# WallLightRemote_V1_0_MCU.net
KiCad netlist of a schematic drawn in Altium Designer
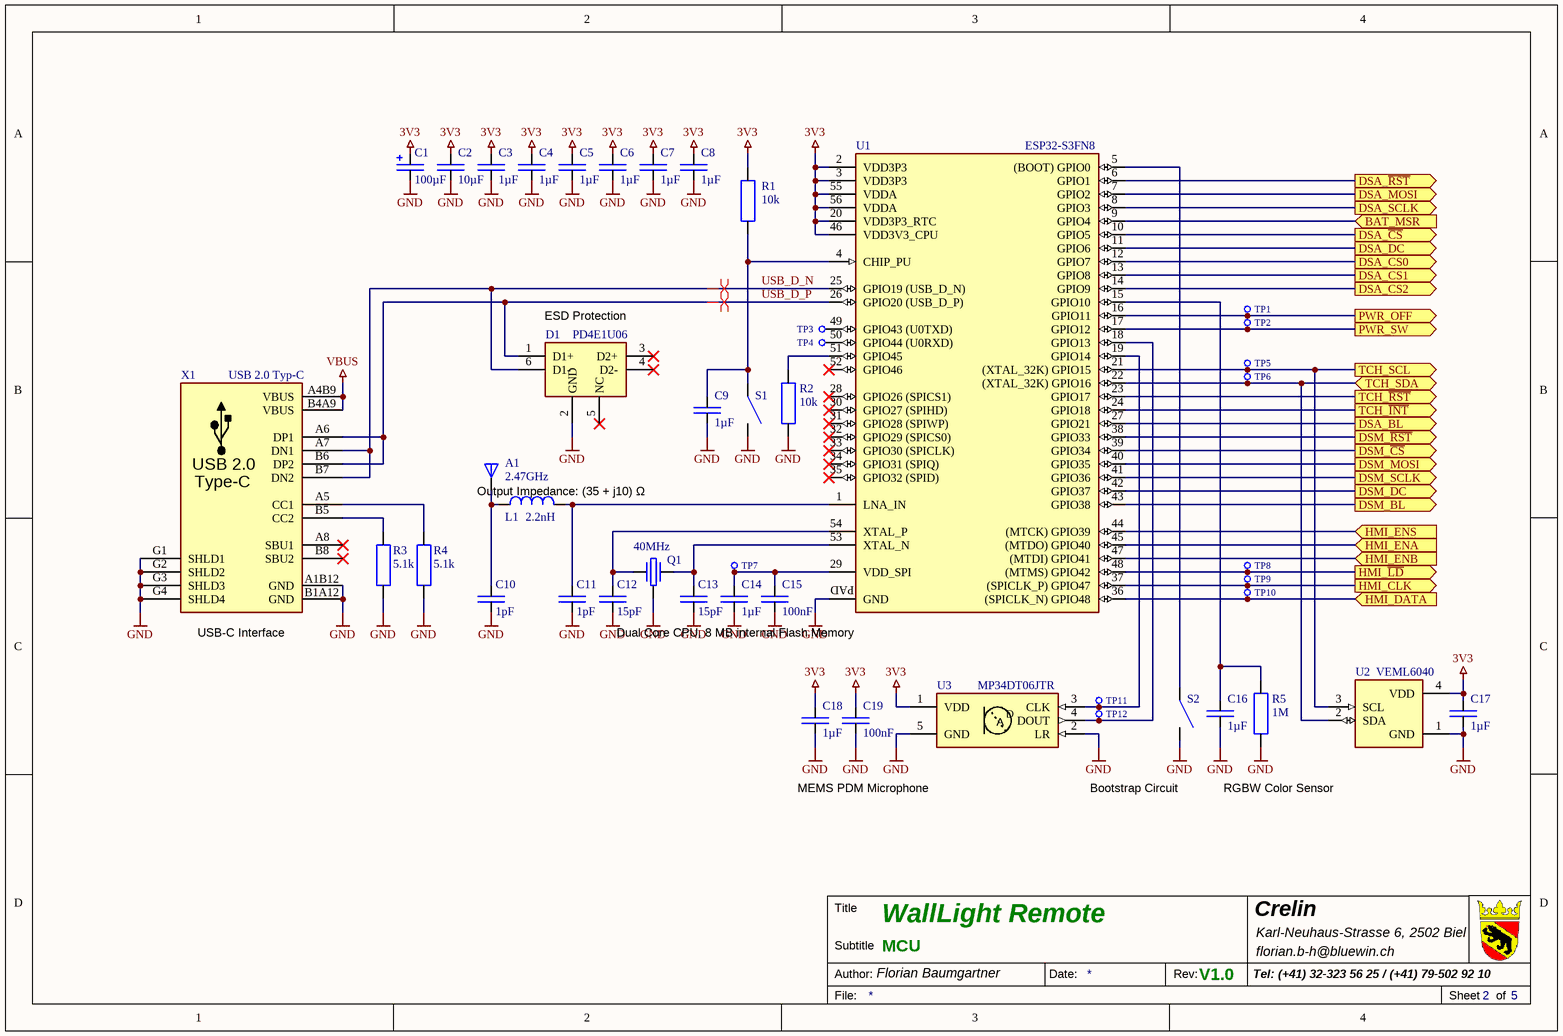
[diagram p0: WallLightRemote_V1.0_MCU.SchDoc]

(export (version "E")
  (design (tool "Eeschema 10.0.6"))
  (components
    (comp (ref "A1")
      (value "2.47GHz")
      (footprint "SMD Chip-Antenna 7020 (SLDA72-2R470G-S1TF)")
      (description "Chip-Antenna")
      (libsource (lib "WallLightRemote") (part "A-Chip-Antenna"))
    )
    (comp (ref "C1")
      (value "100µF")
      (footprint "SMD Tantalkondensator 1210 +")
      (description "CAP-Elko")
      (libsource (lib "TFS Integrated Library") (part "C-ELCAP"))
    )
    (comp (ref "C2")
      (value "10µF")
      (footprint "SMD Keramikkondensator 1206")
      (description "SMD Ceramic Capacitor E6")
      (libsource (lib "Ceramic Capacitors-E6") (part "E6 - 10uF"))
    )
    (comp (ref "C3")
      (value "1µF")
      (footprint "SMD Keramikkondensator 0603")
      (description "CAP-MK")
      (libsource (lib "AudioAmp") (part "C-CAPACITOR"))
    )
    (comp (ref "C4")
      (value "1µF")
      (footprint "SMD Keramikkondensator 0603")
      (description "CAP-MK")
      (libsource (lib "AudioAmp") (part "C-CAPACITOR"))
    )
    (comp (ref "C5")
      (value "1µF")
      (footprint "SMD Keramikkondensator 0603")
      (description "CAP-MK")
      (libsource (lib "AudioAmp") (part "C-CAPACITOR"))
    )
    (comp (ref "C6")
      (value "1µF")
      (footprint "SMD Keramikkondensator 0603")
      (description "CAP-MK")
      (libsource (lib "AudioAmp") (part "C-CAPACITOR"))
    )
    (comp (ref "C7")
      (value "1µF")
      (footprint "SMD Keramikkondensator 0603")
      (description "CAP-MK")
      (libsource (lib "AudioAmp") (part "C-CAPACITOR"))
    )
    (comp (ref "C8")
      (value "1µF")
      (footprint "SMD Keramikkondensator 0603")
      (description "CAP-MK")
      (libsource (lib "AudioAmp") (part "C-CAPACITOR"))
    )
    (comp (ref "C9")
      (value "1µF")
      (footprint "SMD Keramikkondensator 0603")
      (description "CAP-MK")
      (libsource (lib "AudioAmp") (part "C-CAPACITOR"))
    )
    (comp (ref "C10")
      (value "1pF")
      (footprint "SMD Keramikkondensator 0402")
      (description "CAP-MK")
      (libsource (lib "AudioAmp") (part "C-CAPACITOR"))
    )
    (comp (ref "C11")
      (value "1pF")
      (footprint "SMD Keramikkondensator 0402")
      (description "CAP-MK")
      (libsource (lib "AudioAmp") (part "C-CAPACITOR"))
    )
    (comp (ref "C12")
      (value "15pF")
      (footprint "SMD Keramikkondensator 0603")
      (description "CAP-MK")
      (libsource (lib "AudioAmp") (part "C-CAPACITOR"))
    )
    (comp (ref "C13")
      (value "15pF")
      (footprint "SMD Keramikkondensator 0603")
      (description "CAP-MK")
      (libsource (lib "AudioAmp") (part "C-CAPACITOR"))
    )
    (comp (ref "C14")
      (value "1µF")
      (footprint "SMD Keramikkondensator 0603")
      (description "CAP-MK")
      (libsource (lib "AudioAmp") (part "C-CAPACITOR"))
    )
    (comp (ref "C15")
      (value "100nF")
      (footprint "SMD Keramikkondensator 0603")
      (description "SMD Ceramic Capacitor E6")
      (libsource (lib "Ceramic Capacitors-E6") (part "E6 - 100nF"))
    )
    (comp (ref "C16")
      (value "1µF")
      (footprint "SMD Keramikkondensator 0603")
      (description "CAP-MK")
      (libsource (lib "AudioAmp") (part "C-CAPACITOR"))
    )
    (comp (ref "C17")
      (value "1µF")
      (footprint "SMD Keramikkondensator 0603")
      (description "CAP-MK")
      (libsource (lib "AudioAmp") (part "C-CAPACITOR"))
    )
    (comp (ref "C18")
      (value "1µF")
      (footprint "SMD Keramikkondensator 0603")
      (description "CAP-MK")
      (libsource (lib "AudioAmp") (part "C-CAPACITOR"))
    )
    (comp (ref "C19")
      (value "100nF")
      (footprint "SMD Keramikkondensator 0603")
      (description "SMD Ceramic Capacitor E6")
      (libsource (lib "Ceramic Capacitors-E6") (part "E6 - 100nF"))
    )
    (comp (ref "D1")
      (value "PD4E1U06")
      (footprint "SMD IC SOT-363 (SC-70-6)")
      (description "Unidirectional 3A (8/20us) 15V (Typ) 6.5V 5.5V (Max) SOT-363 ESD Protection Devices ROHS")
      (libsource (lib "Fleet-Monitor") (part "PD4E1U06DCKR"))
    )
    (comp (ref "L1")
      (value "2.2nH")
      (footprint "SMD Inductor 0402")
      (description "Chip Inductor")
      (libsource (lib "TFS Integrated Library") (part "R-COIL (HF)"))
    )
    (comp (ref "Q1")
      (value "40MHz")
      (footprint "SMD Crystal 2.5X2.0X0.5")
      (libsource (lib "WallLightRemote") (part "B-QUARZ-CAP"))
    )
    (comp (ref "R1")
      (value "10k")
      (footprint "SMD Widerstand 0603")
      (description "RES (E=Heizwiderstand B=Messwandler)")
      (libsource (lib "") (part "R-RESISTOR_1"))
    )
    (comp (ref "R2")
      (value "10k")
      (footprint "SMD Widerstand 0603")
      (description "RES (E=Heizwiderstand B=Messwandler)")
      (libsource (lib "") (part "R-RESISTOR_1"))
    )
    (comp (ref "R3")
      (value "5.1k")
      (footprint "SMD Widerstand 0603")
      (description "RES (E=Heizwiderstand B=Messwandler)")
      (libsource (lib "TFS Integrated Library") (part "R-RESISTOR"))
    )
    (comp (ref "R4")
      (value "5.1k")
      (footprint "SMD Widerstand 0603")
      (description "RES (E=Heizwiderstand B=Messwandler)")
      (libsource (lib "TFS Integrated Library") (part "R-RESISTOR"))
    )
    (comp (ref "R5")
      (value "1M")
      (footprint "SMD Widerstand 0603")
      (description "RES (E=Heizwiderstand B=Messwandler)")
      (libsource (lib "") (part "R-RESISTOR_2"))
    )
    (comp (ref "S1")
      (value "SMD-Button")
      (footprint "SMD Button 4.2x3.2x2.5")
      (description "Button SPST")
      (libsource (lib "Switches") (part "Button 3mmx2.5mm"))
    )
    (comp (ref "S2")
      (value "SMD-Button")
      (footprint "SMD Button 4.2x3.2x2.5")
      (description "Button SPST")
      (libsource (lib "Switches") (part "Button 3mmx2.5mm"))
    )
    (comp (ref "TP1")
      (value "X-TP")
      (footprint "SMD Testpunkt Ø1mm")
      (description "Testpunkt")
      (libsource (lib "VLD-Monitor_V1.0") (part "X-TP"))
    )
    (comp (ref "TP2")
      (value "X-TP")
      (footprint "SMD Testpunkt Ø1mm")
      (description "Testpunkt")
      (libsource (lib "VLD-Monitor_V1.0") (part "X-TP"))
    )
    (comp (ref "TP3")
      (value "X-TP")
      (footprint "SMD Testpunkt Ø1mm")
      (description "Testpunkt")
      (libsource (lib "VLD-Monitor_V1.0") (part "X-TP"))
    )
    (comp (ref "TP4")
      (value "X-TP")
      (footprint "SMD Testpunkt Ø1mm")
      (description "Testpunkt")
      (libsource (lib "VLD-Monitor_V1.0") (part "X-TP"))
    )
    (comp (ref "TP5")
      (value "X-TP")
      (footprint "SMD Testpunkt Ø1mm")
      (description "Testpunkt")
      (libsource (lib "VLD-Monitor_V1.0") (part "X-TP"))
    )
    (comp (ref "TP6")
      (value "X-TP")
      (footprint "SMD Testpunkt Ø1mm")
      (description "Testpunkt")
      (libsource (lib "VLD-Monitor_V1.0") (part "X-TP"))
    )
    (comp (ref "TP7")
      (value "X-TP")
      (footprint "SMD Testpunkt Ø1mm")
      (description "Testpunkt")
      (libsource (lib "VLD-Monitor_V1.0") (part "X-TP"))
    )
    (comp (ref "TP8")
      (value "X-TP")
      (footprint "SMD Testpunkt Ø1mm")
      (description "Testpunkt")
      (libsource (lib "VLD-Monitor_V1.0") (part "X-TP"))
    )
    (comp (ref "TP9")
      (value "X-TP")
      (footprint "SMD Testpunkt Ø1mm")
      (description "Testpunkt")
      (libsource (lib "VLD-Monitor_V1.0") (part "X-TP"))
    )
    (comp (ref "TP10")
      (value "X-TP")
      (footprint "SMD Testpunkt Ø1mm")
      (description "Testpunkt")
      (libsource (lib "VLD-Monitor_V1.0") (part "X-TP"))
    )
    (comp (ref "TP11")
      (value "X-TP")
      (footprint "SMD Testpunkt Ø1mm")
      (description "Testpunkt")
      (libsource (lib "VLD-Monitor_V1.0") (part "X-TP"))
    )
    (comp (ref "TP12")
      (value "X-TP")
      (footprint "SMD Testpunkt Ø1mm")
      (description "Testpunkt")
      (libsource (lib "VLD-Monitor_V1.0") (part "X-TP"))
    )
    (comp (ref "U1")
      (value "ESP32-S3FN8")
      (footprint "SMD IC QFN-56 (0.4mm)")
      (description "2.4 GHz Wi­Fi + Bluetooth® LE SoC")
      (libsource (lib "WallLightRemote") (part "U-ESP32-S3FN8"))
    )
    (comp (ref "U2")
      (value "VEML6040")
      (footprint "SMD Color Sensor (VEML6040)")
      (description "RGBW Color Sensor with I2C Interface")
      (libsource (lib "WallLightRemote") (part "U-VEML6040"))
    )
    (comp (ref "U3")
      (value "MP34DT06JTR")
      (footprint "SMD Microphone (MP34DT06JTR)")
      (description "Digital PDM MEMS Microphone")
      (libsource (lib "WallLightRemote") (part "U-MP34DT06JTR"))
    )
    (comp (ref "X1")
      (value "USB 2.0 Typ-C")
      (footprint "SMD USB-C Socket (A40-00119)")
      (description "Typ-C")
      (libsource (lib "Custom ST-Link") (part "X-USB-Buchse"))
    )
  )
  (nets
    (net (code "1") (name "/BAT_MSR") (class "Default")
      (node (ref "U1") (pin "9") (pinfunction "GPIO4_9") (pintype "bidirectional"))
    )
    (net (code "2") (name "/DSA_BL") (class "Default")
      (node (ref "U1") (pin "27") (pinfunction "GPIO21_27") (pintype "bidirectional"))
    )
    (net (code "3") (name "/DSA_CS0") (class "Default")
      (node (ref "U1") (pin "12") (pinfunction "GPIO7_12") (pintype "bidirectional"))
    )
    (net (code "4") (name "/DSA_CS1") (class "Default")
      (node (ref "U1") (pin "13") (pinfunction "GPIO8_13") (pintype "bidirectional"))
    )
    (net (code "5") (name "/DSA_CS2") (class "Default")
      (node (ref "U1") (pin "14") (pinfunction "GPIO9_14") (pintype "bidirectional"))
    )
    (net (code "6") (name "/DSA_DC") (class "Default")
      (node (ref "U1") (pin "11") (pinfunction "GPIO6_11") (pintype "bidirectional"))
    )
    (net (code "7") (name "/DSA_MOSI") (class "Default")
      (node (ref "U1") (pin "7") (pinfunction "GPIO2_7") (pintype "bidirectional"))
    )
    (net (code "8") (name "/DSA_SCLK") (class "Default")
      (node (ref "U1") (pin "8") (pinfunction "GPIO3_8") (pintype "bidirectional"))
    )
    (net (code "9") (name "/DSA_~{CS}") (class "Default")
      (node (ref "U1") (pin "10") (pinfunction "GPIO5_10") (pintype "bidirectional"))
    )
    (net (code "10") (name "/DSA_~{RST}") (class "Default")
      (node (ref "U1") (pin "6") (pinfunction "GPIO1_6") (pintype "bidirectional"))
    )
    (net (code "11") (name "/DSM_BL") (class "Default")
      (node (ref "U1") (pin "43") (pinfunction "GPIO38_43") (pintype "bidirectional"))
    )
    (net (code "12") (name "/DSM_DC") (class "Default")
      (node (ref "U1") (pin "42") (pinfunction "GPIO37_42") (pintype "bidirectional"))
    )
    (net (code "13") (name "/DSM_MOSI") (class "Default")
      (node (ref "U1") (pin "40") (pinfunction "GPIO35_40") (pintype "bidirectional"))
    )
    (net (code "14") (name "/DSM_SCLK") (class "Default")
      (node (ref "U1") (pin "41") (pinfunction "GPIO36_41") (pintype "bidirectional"))
    )
    (net (code "15") (name "/DSM_~{CS}") (class "Default")
      (node (ref "U1") (pin "39") (pinfunction "GPIO34_39") (pintype "bidirectional"))
    )
    (net (code "16") (name "/DSM_~{RST}") (class "Default")
      (node (ref "U1") (pin "38") (pinfunction "GPIO33_38") (pintype "bidirectional"))
    )
    (net (code "17") (name "/HMI_CLK") (class "Default")
      (node (ref "TP9") (pin "1") (pinfunction "1_1") (pintype "passive"))
      (node (ref "U1") (pin "37") (pinfunction "(SPICLK_P)_GPIO47_37") (pintype "bidirectional"))
    )
    (net (code "18") (name "/HMI_DATA") (class "Default")
      (node (ref "TP10") (pin "1") (pinfunction "1_1") (pintype "passive"))
      (node (ref "U1") (pin "36") (pinfunction "(SPICLK_N)_GPIO48_36") (pintype "bidirectional"))
    )
    (net (code "19") (name "/HMI_ENA") (class "Default")
      (node (ref "U1") (pin "45") (pinfunction "(MTDO)_GPIO40_45") (pintype "bidirectional"))
    )
    (net (code "20") (name "/HMI_ENB") (class "Default")
      (node (ref "U1") (pin "47") (pinfunction "(MTDI)_GPIO41_47") (pintype "bidirectional"))
    )
    (net (code "21") (name "/HMI_ENS") (class "Default")
      (node (ref "U1") (pin "44") (pinfunction "(MTCK)_GPIO39_44") (pintype "bidirectional"))
    )
    (net (code "22") (name "/HMI_~{LD}") (class "Default")
      (node (ref "TP8") (pin "1") (pinfunction "1_1") (pintype "passive"))
      (node (ref "U1") (pin "48") (pinfunction "(MTMS)_GPIO42_48") (pintype "bidirectional"))
    )
    (net (code "23") (name "/PWR_OFF") (class "Default")
      (node (ref "TP1") (pin "1") (pinfunction "1_1") (pintype "passive"))
      (node (ref "U1") (pin "16") (pinfunction "GPIO11_16") (pintype "bidirectional"))
    )
    (net (code "24") (name "/PWR_SW") (class "Default")
      (node (ref "TP2") (pin "1") (pinfunction "1_1") (pintype "passive"))
      (node (ref "U1") (pin "17") (pinfunction "GPIO12_17") (pintype "bidirectional"))
    )
    (net (code "25") (name "/TCH_SCL") (class "Default")
      (node (ref "TP5") (pin "1") (pinfunction "1_1") (pintype "passive"))
      (node (ref "U1") (pin "21") (pinfunction "(XTAL_32K)_GPIO15_21") (pintype "bidirectional"))
      (node (ref "U2") (pin "3") (pinfunction "SCL_3") (pintype "input"))
    )
    (net (code "26") (name "/TCH_SDA") (class "Default")
      (node (ref "TP6") (pin "1") (pinfunction "1_1") (pintype "passive"))
      (node (ref "U1") (pin "22") (pinfunction "(XTAL_32K)_GPIO16_22") (pintype "bidirectional"))
      (node (ref "U2") (pin "2") (pinfunction "SDA_2") (pintype "bidirectional"))
    )
    (net (code "27") (name "/TCH_~{INT}") (class "Default")
      (node (ref "U1") (pin "24") (pinfunction "GPIO18_24") (pintype "bidirectional"))
    )
    (net (code "28") (name "/TCH_~{RST}") (class "Default")
      (node (ref "U1") (pin "23") (pinfunction "GPIO17_23") (pintype "bidirectional"))
    )
    (net (code "29") (name "/USB_D_N") (class "Default")
      (node (ref "D1") (pin "6") (pinfunction "D1-_6") (pintype "passive"))
      (node (ref "U1") (pin "25") (pinfunction "GPIO19_(USB_D_N)_25") (pintype "bidirectional"))
      (node (ref "X1") (pin "A7") (pinfunction "DN1_A7") (pintype "passive"))
      (node (ref "X1") (pin "B7") (pinfunction "DN2_B7") (pintype "passive"))
    )
    (net (code "30") (name "/USB_D_P") (class "Default")
      (node (ref "D1") (pin "1") (pinfunction "D1+_1") (pintype "passive"))
      (node (ref "U1") (pin "26") (pinfunction "GPIO20_(USB_D_P)_26") (pintype "bidirectional"))
      (node (ref "X1") (pin "A6") (pinfunction "DP1_A6") (pintype "passive"))
      (node (ref "X1") (pin "B6") (pinfunction "DP2_B6") (pintype "passive"))
    )
    (net (code "31") (name "3V3") (class "Default")
      (node (ref "C1") (pin "P") (pinfunction "+_P") (pintype "passive"))
      (node (ref "C17") (pin "2") (pinfunction "2_2") (pintype "passive"))
      (node (ref "C18") (pin "2") (pinfunction "2_2") (pintype "passive"))
      (node (ref "C19") (pin "2") (pinfunction "2_2") (pintype "passive"))
      (node (ref "C2") (pin "2") (pinfunction "2_2") (pintype "passive"))
      (node (ref "C3") (pin "2") (pinfunction "2_2") (pintype "passive"))
      (node (ref "C4") (pin "2") (pinfunction "2_2") (pintype "passive"))
      (node (ref "C5") (pin "2") (pinfunction "2_2") (pintype "passive"))
      (node (ref "C6") (pin "2") (pinfunction "2_2") (pintype "passive"))
      (node (ref "C7") (pin "2") (pinfunction "2_2") (pintype "passive"))
      (node (ref "C8") (pin "2") (pinfunction "2_2") (pintype "passive"))
      (node (ref "R1") (pin "2") (pinfunction "2_2") (pintype "passive"))
      (node (ref "U1") (pin "2") (pinfunction "VDD3P3_2") (pintype "power_in"))
      (node (ref "U1") (pin "20") (pinfunction "VDD3P3_RTC_20") (pintype "power_in"))
      (node (ref "U1") (pin "3") (pinfunction "VDD3P3_3") (pintype "power_in"))
      (node (ref "U1") (pin "46") (pinfunction "VDD3V3_CPU_46") (pintype "power_in"))
      (node (ref "U1") (pin "55") (pinfunction "VDDA_55") (pintype "power_in"))
      (node (ref "U1") (pin "56") (pinfunction "VDDA_56") (pintype "power_in"))
      (node (ref "U2") (pin "4") (pinfunction "VDD_4") (pintype "power_in"))
      (node (ref "U3") (pin "1") (pinfunction "VDD_1") (pintype "power_in"))
    )
    (net (code "32") (name "GND") (class "Default")
      (node (ref "C1") (pin "M") (pinfunction "-_M") (pintype "passive"))
      (node (ref "C10") (pin "2") (pinfunction "2_2") (pintype "passive"))
      (node (ref "C11") (pin "2") (pinfunction "2_2") (pintype "passive"))
      (node (ref "C12") (pin "2") (pinfunction "2_2") (pintype "passive"))
      (node (ref "C13") (pin "2") (pinfunction "2_2") (pintype "passive"))
      (node (ref "C14") (pin "1") (pinfunction "1_1") (pintype "passive"))
      (node (ref "C15") (pin "1") (pinfunction "1_1") (pintype "passive"))
      (node (ref "C16") (pin "1") (pinfunction "1_1") (pintype "passive"))
      (node (ref "C17") (pin "1") (pinfunction "1_1") (pintype "passive"))
      (node (ref "C18") (pin "1") (pinfunction "1_1") (pintype "passive"))
      (node (ref "C19") (pin "1") (pinfunction "1_1") (pintype "passive"))
      (node (ref "C2") (pin "1") (pinfunction "1_1") (pintype "passive"))
      (node (ref "C3") (pin "1") (pinfunction "1_1") (pintype "passive"))
      (node (ref "C4") (pin "1") (pinfunction "1_1") (pintype "passive"))
      (node (ref "C5") (pin "1") (pinfunction "1_1") (pintype "passive"))
      (node (ref "C6") (pin "1") (pinfunction "1_1") (pintype "passive"))
      (node (ref "C7") (pin "1") (pinfunction "1_1") (pintype "passive"))
      (node (ref "C8") (pin "1") (pinfunction "1_1") (pintype "passive"))
      (node (ref "C9") (pin "1") (pinfunction "1_1") (pintype "passive"))
      (node (ref "D1") (pin "2") (pinfunction "GND_2") (pintype "passive"))
      (node (ref "Q1") (pin "3") (pinfunction "3_3") (pintype "passive"))
      (node (ref "R2") (pin "1") (pinfunction "1_1") (pintype "passive"))
      (node (ref "R3") (pin "2") (pinfunction "2_2") (pintype "passive"))
      (node (ref "R4") (pin "2") (pinfunction "2_2") (pintype "passive"))
      (node (ref "R5") (pin "1") (pinfunction "1_1") (pintype "passive"))
      (node (ref "S1") (pin "2") (pinfunction "2_2") (pintype "passive"))
      (node (ref "S2") (pin "2") (pinfunction "2_2") (pintype "passive"))
      (node (ref "U1") (pin "PAD") (pinfunction "GND_PAD") (pintype "power_in"))
      (node (ref "U2") (pin "1") (pinfunction "GND_1") (pintype "power_in"))
      (node (ref "U3") (pin "2") (pinfunction "LR_2") (pintype "input"))
      (node (ref "U3") (pin "5") (pinfunction "GND_5") (pintype "power_in"))
      (node (ref "X1") (pin "A1B12") (pinfunction "GND_A1B12") (pintype "passive"))
      (node (ref "X1") (pin "B1A12") (pinfunction "GND_B1A12") (pintype "passive"))
      (node (ref "X1") (pin "G1") (pinfunction "SHLD1_G1") (pintype "passive"))
      (node (ref "X1") (pin "G2") (pinfunction "SHLD2_G2") (pintype "passive"))
      (node (ref "X1") (pin "G3") (pinfunction "SHLD3_G3") (pintype "passive"))
      (node (ref "X1") (pin "G4") (pinfunction "SHLD4_G4") (pintype "passive"))
    )
    (net (code "33") (name "Net-(A1-Pad1)") (class "Default")
      (node (ref "A1") (pin "1") (pinfunction "1_1") (pintype "passive"))
      (node (ref "C10") (pin "1") (pinfunction "1_1") (pintype "passive"))
      (node (ref "L1") (pin "1") (pinfunction "1_1") (pintype "passive"))
    )
    (net (code "34") (name "Net-(U1-(BOOT)_GPIO0)") (class "Default")
      (node (ref "S2") (pin "1") (pinfunction "1_1") (pintype "passive"))
      (node (ref "U1") (pin "5") (pinfunction "(BOOT)_GPIO0_5") (pintype "bidirectional"))
    )
    (net (code "35") (name "Net-(U1-CHIP_PU)") (class "Default")
      (node (ref "C9") (pin "2") (pinfunction "2_2") (pintype "passive"))
      (node (ref "R1") (pin "1") (pinfunction "1_1") (pintype "passive"))
      (node (ref "S1") (pin "1") (pinfunction "1_1") (pintype "passive"))
      (node (ref "U1") (pin "4") (pinfunction "CHIP_PU_4") (pintype "input"))
    )
    (net (code "36") (name "Net-(U1-GPIO10)") (class "Default")
      (node (ref "C16") (pin "2") (pinfunction "2_2") (pintype "passive"))
      (node (ref "R5") (pin "2") (pinfunction "2_2") (pintype "passive"))
      (node (ref "U1") (pin "15") (pinfunction "GPIO10_15") (pintype "bidirectional"))
    )
    (net (code "37") (name "Net-(U1-GPIO13)") (class "Default")
      (node (ref "TP12") (pin "1") (pinfunction "1_1") (pintype "passive"))
      (node (ref "U1") (pin "18") (pinfunction "GPIO13_18") (pintype "bidirectional"))
      (node (ref "U3") (pin "4") (pinfunction "DOUT_4") (pintype "output"))
    )
    (net (code "38") (name "Net-(U1-GPIO14)") (class "Default")
      (node (ref "TP11") (pin "1") (pinfunction "1_1") (pintype "passive"))
      (node (ref "U1") (pin "19") (pinfunction "GPIO14_19") (pintype "bidirectional"))
      (node (ref "U3") (pin "3") (pinfunction "CLK_3") (pintype "input"))
    )
    (net (code "39") (name "Net-(U1-GPIO43_(U0TXD))") (class "Default")
      (node (ref "TP3") (pin "1") (pinfunction "1_1") (pintype "passive"))
      (node (ref "U1") (pin "49") (pinfunction "GPIO43_(U0TXD)_49") (pintype "bidirectional"))
    )
    (net (code "40") (name "Net-(U1-GPIO44_(U0RXD))") (class "Default")
      (node (ref "TP4") (pin "1") (pinfunction "1_1") (pintype "passive"))
      (node (ref "U1") (pin "50") (pinfunction "GPIO44_(U0RXD)_50") (pintype "bidirectional"))
    )
    (net (code "41") (name "Net-(U1-GPIO45)") (class "Default")
      (node (ref "R2") (pin "2") (pinfunction "2_2") (pintype "passive"))
      (node (ref "U1") (pin "51") (pinfunction "GPIO45_51") (pintype "bidirectional"))
    )
    (net (code "42") (name "Net-(U1-LNA_IN)") (class "Default")
      (node (ref "C11") (pin "1") (pinfunction "1_1") (pintype "passive"))
      (node (ref "L1") (pin "2") (pinfunction "2_2") (pintype "passive"))
      (node (ref "U1") (pin "1") (pinfunction "LNA_IN_1") (pintype "passive"))
    )
    (net (code "43") (name "Net-(U1-VDD_SPI)") (class "Default")
      (node (ref "C14") (pin "2") (pinfunction "2_2") (pintype "passive"))
      (node (ref "C15") (pin "2") (pinfunction "2_2") (pintype "passive"))
      (node (ref "TP7") (pin "1") (pinfunction "1_1") (pintype "passive"))
      (node (ref "U1") (pin "29") (pinfunction "VDD_SPI_29") (pintype "power_in"))
    )
    (net (code "44") (name "Net-(U1-XTAL_N)") (class "Default")
      (node (ref "C13") (pin "1") (pinfunction "1_1") (pintype "passive"))
      (node (ref "Q1") (pin "2") (pinfunction "2_2") (pintype "passive"))
      (node (ref "U1") (pin "53") (pinfunction "XTAL_N_53") (pintype "passive"))
    )
    (net (code "45") (name "Net-(U1-XTAL_P)") (class "Default")
      (node (ref "C12") (pin "1") (pinfunction "1_1") (pintype "passive"))
      (node (ref "Q1") (pin "1") (pinfunction "1_1") (pintype "passive"))
      (node (ref "U1") (pin "54") (pinfunction "XTAL_P_54") (pintype "passive"))
    )
    (net (code "46") (name "Net-(X1-CC1)") (class "Default")
      (node (ref "R4") (pin "1") (pinfunction "1_1") (pintype "passive"))
      (node (ref "X1") (pin "A5") (pinfunction "CC1_A5") (pintype "passive"))
    )
    (net (code "47") (name "Net-(X1-CC2)") (class "Default")
      (node (ref "R3") (pin "1") (pinfunction "1_1") (pintype "passive"))
      (node (ref "X1") (pin "B5") (pinfunction "CC2_B5") (pintype "passive"))
    )
    (net (code "48") (name "VBUS") (class "Default")
      (node (ref "X1") (pin "A4B9") (pinfunction "VBUS_A4B9") (pintype "passive"))
      (node (ref "X1") (pin "B4A9") (pinfunction "VBUS_B4A9") (pintype "passive"))
    )
    (net (code "49") (name "unconnected-(D1-D2+-Pad3)") (class "Default")
      (node (ref "D1") (pin "3") (pinfunction "D2+_3") (pintype "passive+no_connect"))
    )
    (net (code "50") (name "unconnected-(D1-D2--Pad4)") (class "Default")
      (node (ref "D1") (pin "4") (pinfunction "D2-_4") (pintype "passive+no_connect"))
    )
    (net (code "51") (name "unconnected-(D1-NC-Pad5)") (class "Default")
      (node (ref "D1") (pin "5") (pinfunction "NC_5") (pintype "passive+no_connect"))
    )
    (net (code "52") (name "unconnected-(U1-GPIO26_(SPICS1)-Pad28)") (class "Default")
      (node (ref "U1") (pin "28") (pinfunction "GPIO26_(SPICS1)_28") (pintype "bidirectional+no_connect"))
    )
    (net (code "53") (name "unconnected-(U1-GPIO27_(SPIHD)-Pad30)") (class "Default")
      (node (ref "U1") (pin "30") (pinfunction "GPIO27_(SPIHD)_30") (pintype "bidirectional+no_connect"))
    )
    (net (code "54") (name "unconnected-(U1-GPIO28_(SPIWP)-Pad31)") (class "Default")
      (node (ref "U1") (pin "31") (pinfunction "GPIO28_(SPIWP)_31") (pintype "bidirectional+no_connect"))
    )
    (net (code "55") (name "unconnected-(U1-GPIO29_(SPICS0)-Pad32)") (class "Default")
      (node (ref "U1") (pin "32") (pinfunction "GPIO29_(SPICS0)_32") (pintype "bidirectional+no_connect"))
    )
    (net (code "56") (name "unconnected-(U1-GPIO30_(SPICLK)-Pad33)") (class "Default")
      (node (ref "U1") (pin "33") (pinfunction "GPIO30_(SPICLK)_33") (pintype "bidirectional+no_connect"))
    )
    (net (code "57") (name "unconnected-(U1-GPIO31_(SPIQ)-Pad34)") (class "Default")
      (node (ref "U1") (pin "34") (pinfunction "GPIO31_(SPIQ)_34") (pintype "bidirectional+no_connect"))
    )
    (net (code "58") (name "unconnected-(U1-GPIO32_(SPID)-Pad35)") (class "Default")
      (node (ref "U1") (pin "35") (pinfunction "GPIO32_(SPID)_35") (pintype "bidirectional+no_connect"))
    )
    (net (code "59") (name "unconnected-(U1-GPIO46-Pad52)") (class "Default")
      (node (ref "U1") (pin "52") (pinfunction "GPIO46_52") (pintype "bidirectional+no_connect"))
    )
    (net (code "60") (name "unconnected-(X1-SBU1-PadA8)") (class "Default")
      (node (ref "X1") (pin "A8") (pinfunction "SBU1_A8") (pintype "passive+no_connect"))
    )
    (net (code "61") (name "unconnected-(X1-SBU2-PadB8)") (class "Default")
      (node (ref "X1") (pin "B8") (pinfunction "SBU2_B8") (pintype "passive+no_connect"))
    )
  )
)
